# Sheet1.net
KiCad netlist of a schematic drawn in Altium Designer
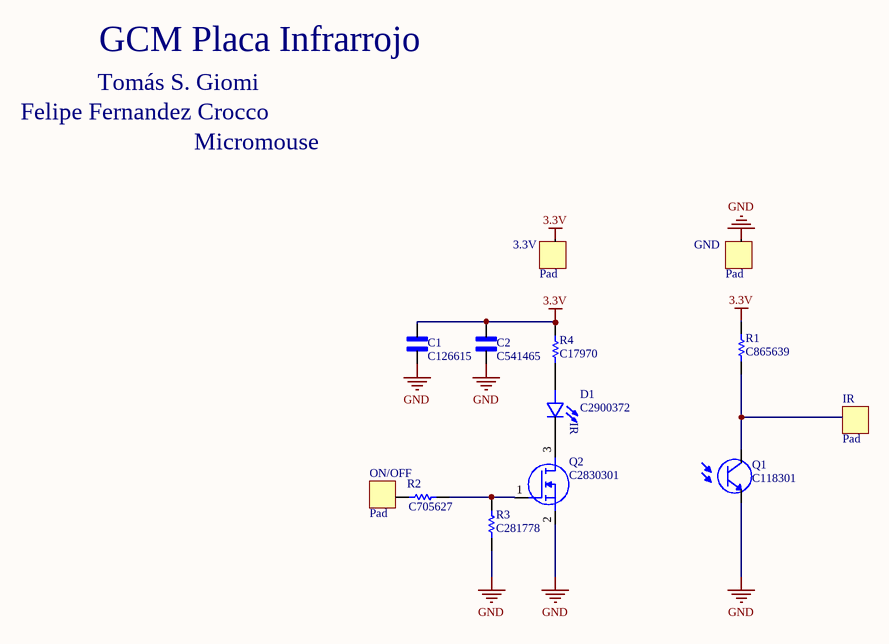
[diagram p0: Sheet1.SchDoc]

(export (version "E")
  (design (tool "Eeschema 10.0.6"))
  (components
    (comp (ref "3.3V") (value "Pad") (footprint "PCBComponent_1") (libsource (lib "Schlib1") (part "Pad")))
    (comp (ref "C1")
      (value "C126615")
      (footprint "CAP_CC1210_YAG")
      (description "Description")
      (fields
        (field (name "MANUFACTURER_PART_NUMBER") "CC1210KKX7R7BB226")
        (field (name "COPYRIGHT") "Copyright (C) 2026 Ultra Librarian. All rights reserved.")
      )
      (libsource (lib "Schlib1") (part "CC1210KKX7R7BB226"))
    )
    (comp (ref "C2")
      (value "C541465")
      (footprint "CAPC1005X55N")
      (description "10000 pF Â±5% 25V Ceramic Capacitor X7R 0402 (1005 Metric)")
      (fields (field (name "MF") "Yageo") (field (name "MP") "CC0402JRX7R8BB103"))
      (libsource (lib "Schlib1") (part "CC0402JRX7R8BB103"))
    )
    (comp (ref "D1")
      (value "C2900372")
      (footprint "DIO_SFH_4545")
      (description "Infrared (IR) Emitter 950nm 1.5V 100mA 550mW/sr @ 100mA 10Â° Radial")
      (fields (field (name "MF") "OSRAM Opto") (field (name "MP") "SFH 4545"))
      (libsource (lib "Schlib1") (part "SFH_4545"))
    )
    (comp (ref "GND") (value "Pad") (footprint "PCBComponent_1") (libsource (lib "Schlib1") (part "Pad")))
    (comp (ref "IR") (value "Pad") (footprint "PCBComponent_1") (libsource (lib "") (part "Pad_1")))
    (comp (ref "ON/OFF") (value "Pad") (footprint "PCBComponent_1") (libsource (lib "") (part "Pad_2")))
    (comp (ref "Q1")
      (value "C118301")
      (footprint "XDCR_TEFT4300")
      (description "Phototransistors 925nm Top View Radial, 3mm Dia (T-1)")
      (fields (field (name "MF") "Vishay Semiconductor") (field (name "MP") "TEFT4300"))
      (libsource (lib "Schlib1") (part "TEFT4300"))
    )
    (comp (ref "Q2")
      (value "C2830301")
      (footprint "SOT50P160X90-3N")
      (description "MOSFET N-Channel 20V 0.63A SOT523 ¦ Diodes Inc DMG1012T-7")
      (fields (field (name "MF") "Diodes Inc.") (field (name "MP") "DMG1012T-7"))
      (libsource (lib "Schlib1") (part "DMG1012T-7"))
    )
    (comp (ref "R1")
      (value "C865639")
      (footprint "RESC2012X60N")
      (description "5.6 Ohm 1/4W Thick Film Resistor 1206 Chip - Surface Mount")
      (fields (field (name "MF") "Uni-Royal") (field (name "MP") "1206W4F560KT5E"))
      (libsource (lib "Schlib1") (part "RT0805BRD07510RL"))
    )
    (comp (ref "R2")
      (value "C705627")
      (footprint "RESC1005X35N")
      (description "RT Series 0402 0.063 W 24 kOhm Â±1 % Â±50 ppm/Â°C SMT Thin Film Chip Resistor")
      (fields (field (name "MF") "Yageo") (field (name "MP") "RT0402FRE0724KL"))
      (libsource (lib "Schlib1") (part "RT0402FRE0724KL"))
    )
    (comp (ref "R3")
      (value "C281778")
      (footprint "RESC1005X35N")
      (description "RT Series 0402 0.063 W 24 kOhm Â±1 % Â±50 ppm/Â°C SMT Thin Film Chip Resistor")
      (fields (field (name "MF") "Yageo") (field (name "MP") "RT0402FRE0724KL"))
      (libsource (lib "Schlib1") (part "RT0402FRE0724KL"))
    )
    (comp (ref "R4")
      (value "C17970")
      (footprint "RESC3115X65N")
      (description "5.6 Ohm 1/4W Thick Film Resistor 1206 Chip - Surface Mount")
      (fields (field (name "MF") "Uni-Royal") (field (name "MP") "1206W4F560KT5E"))
      (libsource (lib "Schlib1") (part "1206W4F560KT5E"))
    )
  )
  (nets
    (net (code "1") (name "3.3V") (class "Default")
      (node (ref "3.3V") (pin "1") (pinfunction "1_1") (pintype "passive"))
      (node (ref "C1") (pin "2") (pinfunction "2_2") (pintype "passive"))
      (node (ref "C2") (pin "2") (pinfunction "2_2") (pintype "passive"))
      (node (ref "R1") (pin "2") (pinfunction "2_2") (pintype "passive"))
      (node (ref "R4") (pin "2") (pinfunction "2_2") (pintype "passive"))
    )
    (net (code "2") (name "GND") (class "Default")
      (node (ref "C1") (pin "1") (pinfunction "1_1") (pintype "passive"))
      (node (ref "C2") (pin "1") (pinfunction "1_1") (pintype "passive"))
      (node (ref "GND") (pin "1") (pinfunction "1_1") (pintype "passive"))
      (node (ref "Q1") (pin "E") (pinfunction "E_E") (pintype "passive"))
      (node (ref "Q2") (pin "2") (pinfunction "S_2") (pintype "bidirectional"))
      (node (ref "R3") (pin "1") (pinfunction "1_1") (pintype "passive"))
    )
    (net (code "3") (name "Net-(D1-PadA)") (class "Default")
      (node (ref "D1") (pin "A") (pinfunction "A_A") (pintype "passive"))
      (node (ref "R4") (pin "1") (pinfunction "1_1") (pintype "passive"))
    )
    (net (code "4") (name "Net-(IR-Pad1)") (class "Default")
      (node (ref "IR") (pin "1") (pinfunction "1_1") (pintype "passive"))
      (node (ref "Q1") (pin "C") (pinfunction "C_C") (pintype "passive"))
      (node (ref "R1") (pin "1") (pinfunction "1_1") (pintype "passive"))
    )
    (net (code "5") (name "Net-(ON/OFF-Pad1)") (class "Default")
      (node (ref "ON/OFF") (pin "1") (pinfunction "1_1") (pintype "passive"))
      (node (ref "R2") (pin "1") (pinfunction "1_1") (pintype "passive"))
    )
    (net (code "6") (name "Net-(Q2-D)") (class "Default")
      (node (ref "D1") (pin "C") (pinfunction "C_C") (pintype "passive"))
      (node (ref "Q2") (pin "3") (pinfunction "D_3") (pintype "bidirectional"))
    )
    (net (code "7") (name "Net-(Q2-G)") (class "Default")
      (node (ref "Q2") (pin "1") (pinfunction "G_1") (pintype "bidirectional"))
      (node (ref "R2") (pin "2") (pinfunction "2_2") (pintype "passive"))
      (node (ref "R3") (pin "2") (pinfunction "2_2") (pintype "passive"))
    )
  )
)
